# JapaneseLayout_OJP_V0_1_Page_2.net
KiCad netlist of a schematic drawn in Altium Designer
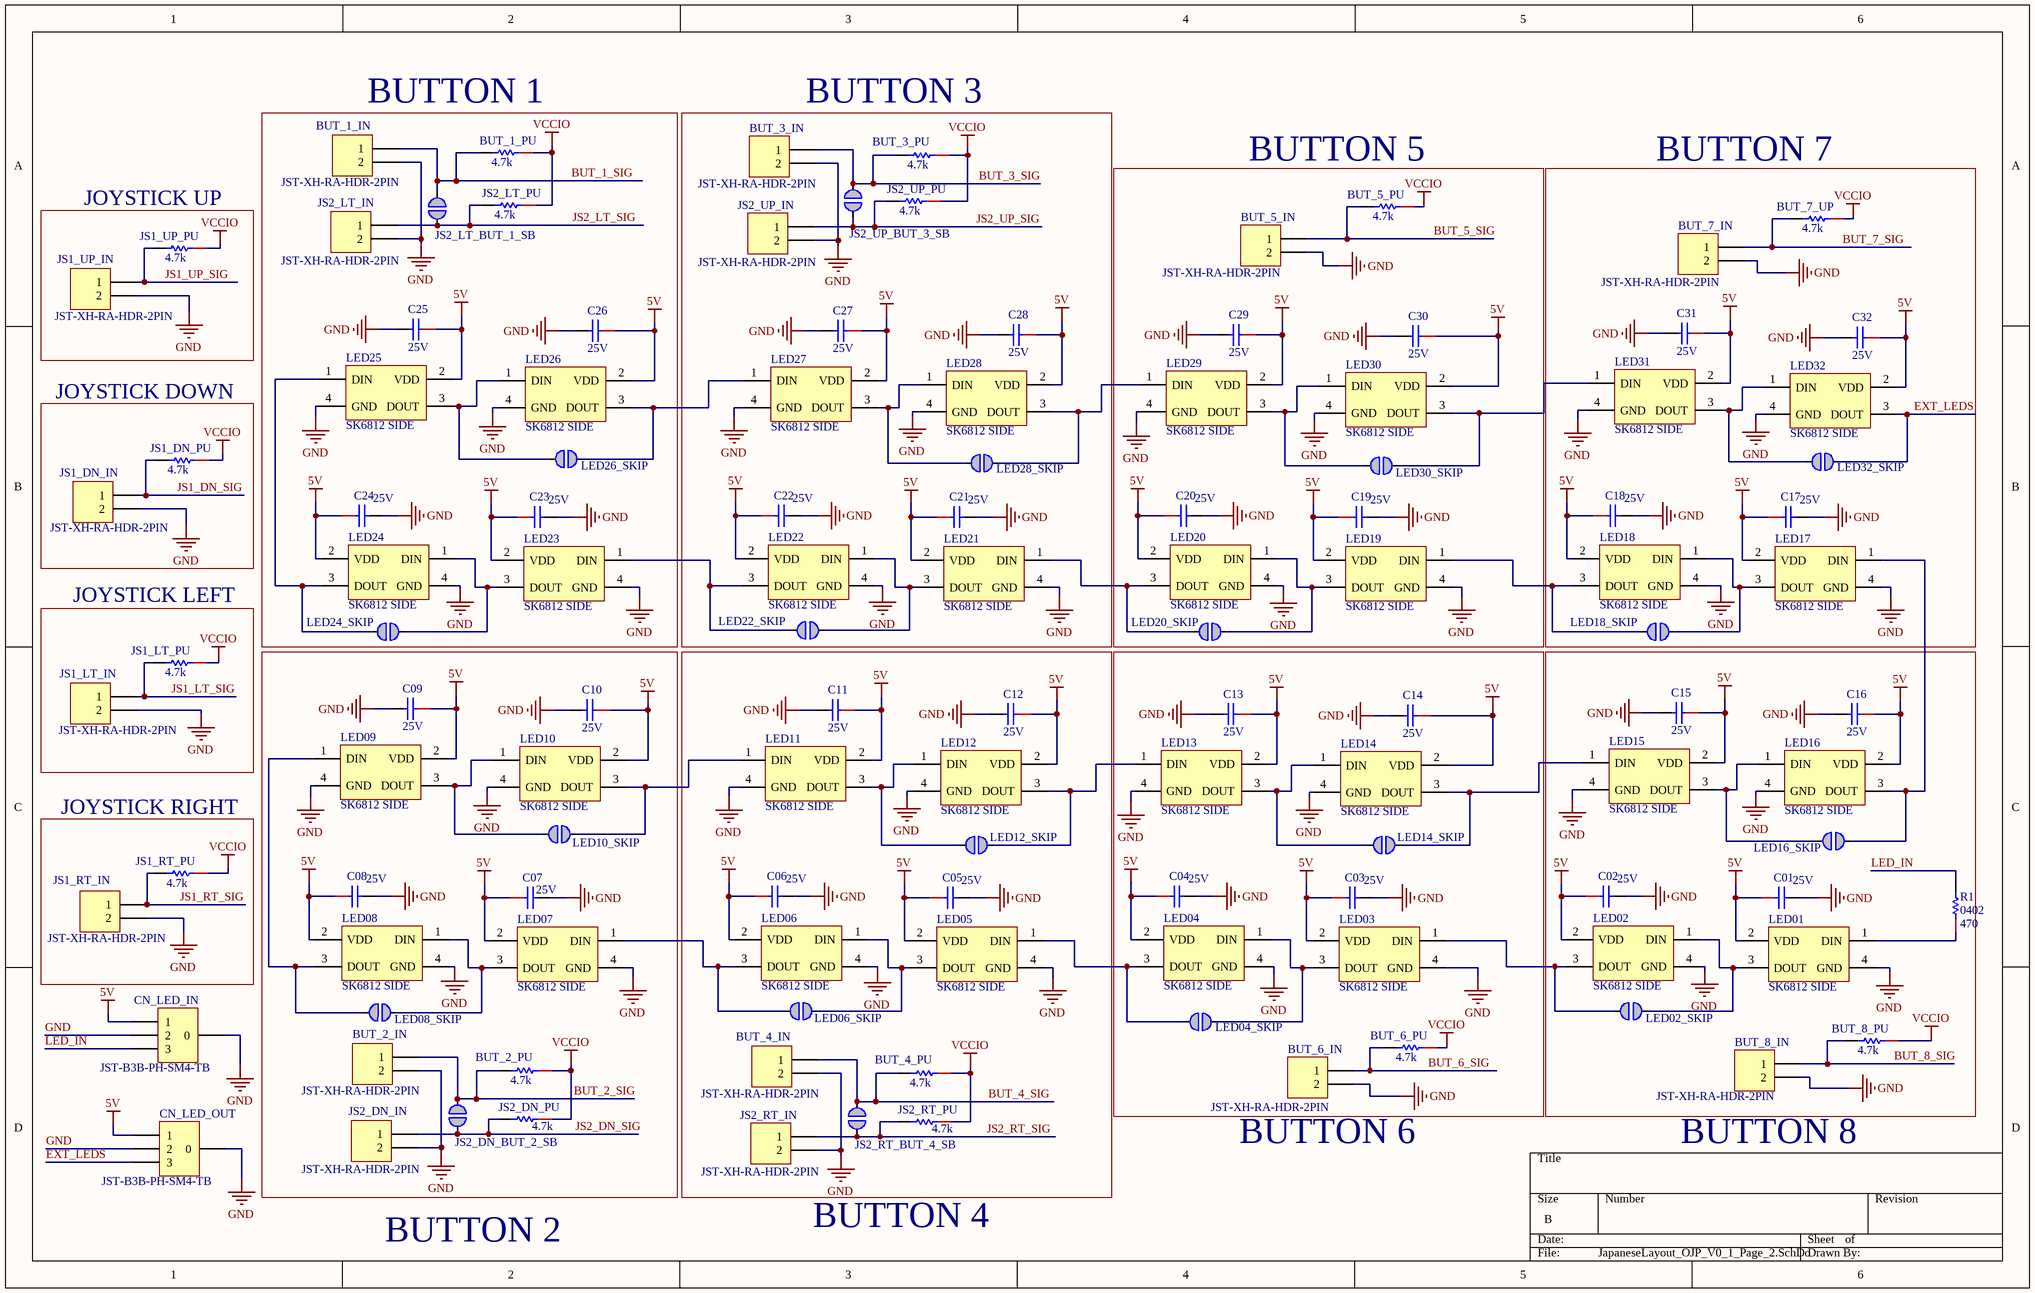
[diagram p0: JapaneseLayout_OJP_V0_1_Page_2.SchDoc]

(export (version "E")
  (design (tool "Eeschema 10.0.6"))
  (components
    (comp (ref "BUT_1_IN")
      (value "JST-XH-RA-HDR-2PIN")
      (footprint "JST-XH-RA-HDR-2PIN")
      (description "2.5 mm JST XH-Style Shrouded Male Connector: 2-Pin, Right Angle; Pololu #2718")
      (libsource (lib "OLogic Nexus Vault") (part "JST-XH-RA-HDR-2PIN"))
    )
    (comp (ref "BUT_1_PU")
      (value "4.7K")
      (footprint "RESC0402(1005)_N")
      (description "RES 4.7K OHM 1% 1/10W 0402")
      (fields
        (field (name "RESISTANCE") "4.7k")
        (field (name "POWER") "100mW")
        (field (name "TOLERANCE") "1%")
      )
      (libsource (lib "OLogic Nexus Vault") (part "=Resistance"))
    )
    (comp (ref "BUT_2_IN")
      (value "JST-XH-RA-HDR-2PIN")
      (footprint "JST-XH-RA-HDR-2PIN")
      (description "2.5 mm JST XH-Style Shrouded Male Connector: 2-Pin, Right Angle; Pololu #2718")
      (libsource (lib "OLogic Nexus Vault") (part "JST-XH-RA-HDR-2PIN"))
    )
    (comp (ref "BUT_2_PU")
      (value "4.7K")
      (footprint "RESC0402(1005)_N")
      (description "RES 4.7K OHM 1% 1/10W 0402")
      (fields
        (field (name "RESISTANCE") "4.7k")
        (field (name "POWER") "100mW")
        (field (name "TOLERANCE") "1%")
      )
      (libsource (lib "OLogic Nexus Vault") (part "=Resistance"))
    )
    (comp (ref "BUT_3_IN")
      (value "JST-XH-RA-HDR-2PIN")
      (footprint "JST-XH-RA-HDR-2PIN")
      (description "2.5 mm JST XH-Style Shrouded Male Connector: 2-Pin, Right Angle; Pololu #2718")
      (libsource (lib "OLogic Nexus Vault") (part "JST-XH-RA-HDR-2PIN"))
    )
    (comp (ref "BUT_3_PU")
      (value "4.7K")
      (footprint "RESC0402(1005)_N")
      (description "RES 4.7K OHM 1% 1/10W 0402")
      (fields
        (field (name "RESISTANCE") "4.7k")
        (field (name "POWER") "100mW")
        (field (name "TOLERANCE") "1%")
      )
      (libsource (lib "OLogic Nexus Vault") (part "=Resistance"))
    )
    (comp (ref "BUT_4_IN")
      (value "JST-XH-RA-HDR-2PIN")
      (footprint "JST-XH-RA-HDR-2PIN")
      (description "2.5 mm JST XH-Style Shrouded Male Connector: 2-Pin, Right Angle; Pololu #2718")
      (libsource (lib "OLogic Nexus Vault") (part "JST-XH-RA-HDR-2PIN"))
    )
    (comp (ref "BUT_4_PU")
      (value "4.7K")
      (footprint "RESC0402(1005)_N")
      (description "RES 4.7K OHM 1% 1/10W 0402")
      (fields
        (field (name "RESISTANCE") "4.7k")
        (field (name "POWER") "100mW")
        (field (name "TOLERANCE") "1%")
      )
      (libsource (lib "OLogic Nexus Vault") (part "=Resistance"))
    )
    (comp (ref "BUT_5_IN")
      (value "JST-XH-RA-HDR-2PIN")
      (footprint "JST-XH-RA-HDR-2PIN")
      (description "2.5 mm JST XH-Style Shrouded Male Connector: 2-Pin, Right Angle; Pololu #2718")
      (libsource (lib "OLogic Nexus Vault") (part "JST-XH-RA-HDR-2PIN"))
    )
    (comp (ref "BUT_5_PU")
      (value "4.7K")
      (footprint "RESC0402(1005)_N")
      (description "RES 4.7K OHM 1% 1/10W 0402")
      (fields
        (field (name "RESISTANCE") "4.7k")
        (field (name "POWER") "100mW")
        (field (name "TOLERANCE") "1%")
      )
      (libsource (lib "OLogic Nexus Vault") (part "=Resistance"))
    )
    (comp (ref "BUT_6_IN")
      (value "JST-XH-RA-HDR-2PIN")
      (footprint "JST-XH-RA-HDR-2PIN")
      (description "2.5 mm JST XH-Style Shrouded Male Connector: 2-Pin, Right Angle; Pololu #2718")
      (libsource (lib "OLogic Nexus Vault") (part "JST-XH-RA-HDR-2PIN"))
    )
    (comp (ref "BUT_6_PU")
      (value "4.7K")
      (footprint "RESC0402(1005)_N")
      (description "RES 4.7K OHM 1% 1/10W 0402")
      (fields
        (field (name "RESISTANCE") "4.7k")
        (field (name "POWER") "100mW")
        (field (name "TOLERANCE") "1%")
      )
      (libsource (lib "OLogic Nexus Vault") (part "=Resistance"))
    )
    (comp (ref "BUT_7_IN")
      (value "JST-XH-RA-HDR-2PIN")
      (footprint "JST-XH-RA-HDR-2PIN")
      (description "2.5 mm JST XH-Style Shrouded Male Connector: 2-Pin, Right Angle; Pololu #2718")
      (libsource (lib "OLogic Nexus Vault") (part "JST-XH-RA-HDR-2PIN"))
    )
    (comp (ref "BUT_7_UP")
      (value "4.7K")
      (footprint "RESC0402(1005)_N")
      (description "RES 4.7K OHM 1% 1/10W 0402")
      (fields
        (field (name "RESISTANCE") "4.7k")
        (field (name "POWER") "100mW")
        (field (name "TOLERANCE") "1%")
      )
      (libsource (lib "OLogic Nexus Vault") (part "=Resistance"))
    )
    (comp (ref "BUT_8_IN")
      (value "JST-XH-RA-HDR-2PIN")
      (footprint "JST-XH-RA-HDR-2PIN")
      (description "2.5 mm JST XH-Style Shrouded Male Connector: 2-Pin, Right Angle; Pololu #2718")
      (libsource (lib "OLogic Nexus Vault") (part "JST-XH-RA-HDR-2PIN"))
    )
    (comp (ref "BUT_8_PU")
      (value "4.7K")
      (footprint "RESC0402(1005)_N")
      (description "RES 4.7K OHM 1% 1/10W 0402")
      (fields
        (field (name "RESISTANCE") "4.7k")
        (field (name "POWER") "100mW")
        (field (name "TOLERANCE") "1%")
      )
      (libsource (lib "OLogic Nexus Vault") (part "=Resistance"))
    )
    (comp (ref "C01")
      (value "CAP CER 0.1UF 25V 10% X5R 0402")
      (footprint "CAPC0402(1005)_N")
      (description "0.1uF 0402 25V")
      (fields
        (field (name "VOLTAGE - RATED") "25V")
        (field (name "MANUFACTURER") "Taiyo Yuden")
        (field (name "MANUFACTURER PART NUMBER") "TMK105BJ104KV-F")
      )
      (libsource (lib "OLogic Nexus Vault") (part "CAP CER 0.1UF 25V 10% X5R 0402"))
    )
    (comp (ref "C02")
      (value "CAP CER 0.1UF 25V 10% X5R 0402")
      (footprint "CAPC0402(1005)_N")
      (description "0.1uF 0402 25V")
      (fields
        (field (name "VOLTAGE - RATED") "25V")
        (field (name "MANUFACTURER") "Taiyo Yuden")
        (field (name "MANUFACTURER PART NUMBER") "TMK105BJ104KV-F")
      )
      (libsource (lib "OLogic Nexus Vault") (part "CAP CER 0.1UF 25V 10% X5R 0402"))
    )
    (comp (ref "C03")
      (value "CAP CER 0.1UF 25V 10% X5R 0402")
      (footprint "CAPC0402(1005)_N")
      (description "0.1uF 0402 25V")
      (fields
        (field (name "VOLTAGE - RATED") "25V")
        (field (name "MANUFACTURER") "Taiyo Yuden")
        (field (name "MANUFACTURER PART NUMBER") "TMK105BJ104KV-F")
      )
      (libsource (lib "OLogic Nexus Vault") (part "CAP CER 0.1UF 25V 10% X5R 0402"))
    )
    (comp (ref "C04")
      (value "CAP CER 0.1UF 25V 10% X5R 0402")
      (footprint "CAPC0402(1005)_N")
      (description "0.1uF 0402 25V")
      (fields
        (field (name "VOLTAGE - RATED") "25V")
        (field (name "MANUFACTURER") "Taiyo Yuden")
        (field (name "MANUFACTURER PART NUMBER") "TMK105BJ104KV-F")
      )
      (libsource (lib "OLogic Nexus Vault") (part "CAP CER 0.1UF 25V 10% X5R 0402"))
    )
    (comp (ref "C05")
      (value "CAP CER 0.1UF 25V 10% X5R 0402")
      (footprint "CAPC0402(1005)_N")
      (description "0.1uF 0402 25V")
      (fields
        (field (name "VOLTAGE - RATED") "25V")
        (field (name "MANUFACTURER") "Taiyo Yuden")
        (field (name "MANUFACTURER PART NUMBER") "TMK105BJ104KV-F")
      )
      (libsource (lib "OLogic Nexus Vault") (part "CAP CER 0.1UF 25V 10% X5R 0402"))
    )
    (comp (ref "C06")
      (value "CAP CER 0.1UF 25V 10% X5R 0402")
      (footprint "CAPC0402(1005)_N")
      (description "0.1uF 0402 25V")
      (fields
        (field (name "VOLTAGE - RATED") "25V")
        (field (name "MANUFACTURER") "Taiyo Yuden")
        (field (name "MANUFACTURER PART NUMBER") "TMK105BJ104KV-F")
      )
      (libsource (lib "OLogic Nexus Vault") (part "CAP CER 0.1UF 25V 10% X5R 0402"))
    )
    (comp (ref "C07")
      (value "CAP CER 0.1UF 25V 10% X5R 0402")
      (footprint "CAPC0402(1005)_N")
      (description "0.1uF 0402 25V")
      (fields
        (field (name "VOLTAGE - RATED") "25V")
        (field (name "MANUFACTURER") "Taiyo Yuden")
        (field (name "MANUFACTURER PART NUMBER") "TMK105BJ104KV-F")
      )
      (libsource (lib "OLogic Nexus Vault") (part "CAP CER 0.1UF 25V 10% X5R 0402"))
    )
    (comp (ref "C08")
      (value "CAP CER 0.1UF 25V 10% X5R 0402")
      (footprint "CAPC0402(1005)_N")
      (description "0.1uF 0402 25V")
      (fields
        (field (name "VOLTAGE - RATED") "25V")
        (field (name "MANUFACTURER") "Taiyo Yuden")
        (field (name "MANUFACTURER PART NUMBER") "TMK105BJ104KV-F")
      )
      (libsource (lib "OLogic Nexus Vault") (part "CAP CER 0.1UF 25V 10% X5R 0402"))
    )
    (comp (ref "C09")
      (value "CAP CER 0.1UF 25V 10% X5R 0402")
      (footprint "CAPC0402(1005)_N")
      (description "0.1uF 0402 25V")
      (fields
        (field (name "VOLTAGE - RATED") "25V")
        (field (name "MANUFACTURER") "Taiyo Yuden")
        (field (name "MANUFACTURER PART NUMBER") "TMK105BJ104KV-F")
      )
      (libsource (lib "OLogic Nexus Vault") (part "CAP CER 0.1UF 25V 10% X5R 0402"))
    )
    (comp (ref "C10")
      (value "CAP CER 0.1UF 25V 10% X5R 0402")
      (footprint "CAPC0402(1005)_N")
      (description "0.1uF 0402 25V")
      (fields
        (field (name "VOLTAGE - RATED") "25V")
        (field (name "MANUFACTURER") "Taiyo Yuden")
        (field (name "MANUFACTURER PART NUMBER") "TMK105BJ104KV-F")
      )
      (libsource (lib "OLogic Nexus Vault") (part "CAP CER 0.1UF 25V 10% X5R 0402"))
    )
    (comp (ref "C11")
      (value "CAP CER 0.1UF 25V 10% X5R 0402")
      (footprint "CAPC0402(1005)_N")
      (description "0.1uF 0402 25V")
      (fields
        (field (name "VOLTAGE - RATED") "25V")
        (field (name "MANUFACTURER") "Taiyo Yuden")
        (field (name "MANUFACTURER PART NUMBER") "TMK105BJ104KV-F")
      )
      (libsource (lib "OLogic Nexus Vault") (part "CAP CER 0.1UF 25V 10% X5R 0402"))
    )
    (comp (ref "C12")
      (value "CAP CER 0.1UF 25V 10% X5R 0402")
      (footprint "CAPC0402(1005)_N")
      (description "0.1uF 0402 25V")
      (fields
        (field (name "VOLTAGE - RATED") "25V")
        (field (name "MANUFACTURER") "Taiyo Yuden")
        (field (name "MANUFACTURER PART NUMBER") "TMK105BJ104KV-F")
      )
      (libsource (lib "OLogic Nexus Vault") (part "CAP CER 0.1UF 25V 10% X5R 0402"))
    )
    (comp (ref "C13")
      (value "CAP CER 0.1UF 25V 10% X5R 0402")
      (footprint "CAPC0402(1005)_N")
      (description "0.1uF 0402 25V")
      (fields
        (field (name "VOLTAGE - RATED") "25V")
        (field (name "MANUFACTURER") "Taiyo Yuden")
        (field (name "MANUFACTURER PART NUMBER") "TMK105BJ104KV-F")
      )
      (libsource (lib "OLogic Nexus Vault") (part "CAP CER 0.1UF 25V 10% X5R 0402"))
    )
    (comp (ref "C14")
      (value "CAP CER 0.1UF 25V 10% X5R 0402")
      (footprint "CAPC0402(1005)_N")
      (description "0.1uF 0402 25V")
      (fields
        (field (name "VOLTAGE - RATED") "25V")
        (field (name "MANUFACTURER") "Taiyo Yuden")
        (field (name "MANUFACTURER PART NUMBER") "TMK105BJ104KV-F")
      )
      (libsource (lib "OLogic Nexus Vault") (part "CAP CER 0.1UF 25V 10% X5R 0402"))
    )
    (comp (ref "C15")
      (value "CAP CER 0.1UF 25V 10% X5R 0402")
      (footprint "CAPC0402(1005)_N")
      (description "0.1uF 0402 25V")
      (fields
        (field (name "VOLTAGE - RATED") "25V")
        (field (name "MANUFACTURER") "Taiyo Yuden")
        (field (name "MANUFACTURER PART NUMBER") "TMK105BJ104KV-F")
      )
      (libsource (lib "OLogic Nexus Vault") (part "CAP CER 0.1UF 25V 10% X5R 0402"))
    )
    (comp (ref "C16")
      (value "CAP CER 0.1UF 25V 10% X5R 0402")
      (footprint "CAPC0402(1005)_N")
      (description "0.1uF 0402 25V")
      (fields
        (field (name "VOLTAGE - RATED") "25V")
        (field (name "MANUFACTURER") "Taiyo Yuden")
        (field (name "MANUFACTURER PART NUMBER") "TMK105BJ104KV-F")
      )
      (libsource (lib "OLogic Nexus Vault") (part "CAP CER 0.1UF 25V 10% X5R 0402"))
    )
    (comp (ref "C17")
      (value "CAP CER 0.1UF 25V 10% X5R 0402")
      (footprint "CAPC0402(1005)_N")
      (description "0.1uF 0402 25V")
      (fields
        (field (name "VOLTAGE - RATED") "25V")
        (field (name "MANUFACTURER") "Taiyo Yuden")
        (field (name "MANUFACTURER PART NUMBER") "TMK105BJ104KV-F")
      )
      (libsource (lib "OLogic Nexus Vault") (part "CAP CER 0.1UF 25V 10% X5R 0402"))
    )
    (comp (ref "C18")
      (value "CAP CER 0.1UF 25V 10% X5R 0402")
      (footprint "CAPC0402(1005)_N")
      (description "0.1uF 0402 25V")
      (fields
        (field (name "VOLTAGE - RATED") "25V")
        (field (name "MANUFACTURER") "Taiyo Yuden")
        (field (name "MANUFACTURER PART NUMBER") "TMK105BJ104KV-F")
      )
      (libsource (lib "OLogic Nexus Vault") (part "CAP CER 0.1UF 25V 10% X5R 0402"))
    )
    (comp (ref "C19")
      (value "CAP CER 0.1UF 25V 10% X5R 0402")
      (footprint "CAPC0402(1005)_N")
      (description "0.1uF 0402 25V")
      (fields
        (field (name "VOLTAGE - RATED") "25V")
        (field (name "MANUFACTURER") "Taiyo Yuden")
        (field (name "MANUFACTURER PART NUMBER") "TMK105BJ104KV-F")
      )
      (libsource (lib "OLogic Nexus Vault") (part "CAP CER 0.1UF 25V 10% X5R 0402"))
    )
    (comp (ref "C20")
      (value "CAP CER 0.1UF 25V 10% X5R 0402")
      (footprint "CAPC0402(1005)_N")
      (description "0.1uF 0402 25V")
      (fields
        (field (name "VOLTAGE - RATED") "25V")
        (field (name "MANUFACTURER") "Taiyo Yuden")
        (field (name "MANUFACTURER PART NUMBER") "TMK105BJ104KV-F")
      )
      (libsource (lib "OLogic Nexus Vault") (part "CAP CER 0.1UF 25V 10% X5R 0402"))
    )
    (comp (ref "C21")
      (value "CAP CER 0.1UF 25V 10% X5R 0402")
      (footprint "CAPC0402(1005)_N")
      (description "0.1uF 0402 25V")
      (fields
        (field (name "VOLTAGE - RATED") "25V")
        (field (name "MANUFACTURER") "Taiyo Yuden")
        (field (name "MANUFACTURER PART NUMBER") "TMK105BJ104KV-F")
      )
      (libsource (lib "OLogic Nexus Vault") (part "CAP CER 0.1UF 25V 10% X5R 0402"))
    )
    (comp (ref "C22")
      (value "CAP CER 0.1UF 25V 10% X5R 0402")
      (footprint "CAPC0402(1005)_N")
      (description "0.1uF 0402 25V")
      (fields
        (field (name "VOLTAGE - RATED") "25V")
        (field (name "MANUFACTURER") "Taiyo Yuden")
        (field (name "MANUFACTURER PART NUMBER") "TMK105BJ104KV-F")
      )
      (libsource (lib "OLogic Nexus Vault") (part "CAP CER 0.1UF 25V 10% X5R 0402"))
    )
    (comp (ref "C23")
      (value "CAP CER 0.1UF 25V 10% X5R 0402")
      (footprint "CAPC0402(1005)_N")
      (description "0.1uF 0402 25V")
      (fields
        (field (name "VOLTAGE - RATED") "25V")
        (field (name "MANUFACTURER") "Taiyo Yuden")
        (field (name "MANUFACTURER PART NUMBER") "TMK105BJ104KV-F")
      )
      (libsource (lib "OLogic Nexus Vault") (part "CAP CER 0.1UF 25V 10% X5R 0402"))
    )
    (comp (ref "C24")
      (value "CAP CER 0.1UF 25V 10% X5R 0402")
      (footprint "CAPC0402(1005)_N")
      (description "0.1uF 0402 25V")
      (fields
        (field (name "VOLTAGE - RATED") "25V")
        (field (name "MANUFACTURER") "Taiyo Yuden")
        (field (name "MANUFACTURER PART NUMBER") "TMK105BJ104KV-F")
      )
      (libsource (lib "OLogic Nexus Vault") (part "CAP CER 0.1UF 25V 10% X5R 0402"))
    )
    (comp (ref "C25")
      (value "CAP CER 0.1UF 25V 10% X5R 0402")
      (footprint "CAPC0402(1005)_N")
      (description "0.1uF 0402 25V")
      (fields
        (field (name "VOLTAGE - RATED") "25V")
        (field (name "MANUFACTURER") "Taiyo Yuden")
        (field (name "MANUFACTURER PART NUMBER") "TMK105BJ104KV-F")
      )
      (libsource (lib "OLogic Nexus Vault") (part "CAP CER 0.1UF 25V 10% X5R 0402"))
    )
    (comp (ref "C26")
      (value "CAP CER 0.1UF 25V 10% X5R 0402")
      (footprint "CAPC0402(1005)_N")
      (description "0.1uF 0402 25V")
      (fields
        (field (name "VOLTAGE - RATED") "25V")
        (field (name "MANUFACTURER") "Taiyo Yuden")
        (field (name "MANUFACTURER PART NUMBER") "TMK105BJ104KV-F")
      )
      (libsource (lib "OLogic Nexus Vault") (part "CAP CER 0.1UF 25V 10% X5R 0402"))
    )
    (comp (ref "C27")
      (value "CAP CER 0.1UF 25V 10% X5R 0402")
      (footprint "CAPC0402(1005)_N")
      (description "0.1uF 0402 25V")
      (fields
        (field (name "VOLTAGE - RATED") "25V")
        (field (name "MANUFACTURER") "Taiyo Yuden")
        (field (name "MANUFACTURER PART NUMBER") "TMK105BJ104KV-F")
      )
      (libsource (lib "OLogic Nexus Vault") (part "CAP CER 0.1UF 25V 10% X5R 0402"))
    )
    (comp (ref "C28")
      (value "CAP CER 0.1UF 25V 10% X5R 0402")
      (footprint "CAPC0402(1005)_N")
      (description "0.1uF 0402 25V")
      (fields
        (field (name "VOLTAGE - RATED") "25V")
        (field (name "MANUFACTURER") "Taiyo Yuden")
        (field (name "MANUFACTURER PART NUMBER") "TMK105BJ104KV-F")
      )
      (libsource (lib "OLogic Nexus Vault") (part "CAP CER 0.1UF 25V 10% X5R 0402"))
    )
    (comp (ref "C29")
      (value "CAP CER 0.1UF 25V 10% X5R 0402")
      (footprint "CAPC0402(1005)_N")
      (description "0.1uF 0402 25V")
      (fields
        (field (name "VOLTAGE - RATED") "25V")
        (field (name "MANUFACTURER") "Taiyo Yuden")
        (field (name "MANUFACTURER PART NUMBER") "TMK105BJ104KV-F")
      )
      (libsource (lib "OLogic Nexus Vault") (part "CAP CER 0.1UF 25V 10% X5R 0402"))
    )
    (comp (ref "C30")
      (value "CAP CER 0.1UF 25V 10% X5R 0402")
      (footprint "CAPC0402(1005)_N")
      (description "0.1uF 0402 25V")
      (fields
        (field (name "VOLTAGE - RATED") "25V")
        (field (name "MANUFACTURER") "Taiyo Yuden")
        (field (name "MANUFACTURER PART NUMBER") "TMK105BJ104KV-F")
      )
      (libsource (lib "OLogic Nexus Vault") (part "CAP CER 0.1UF 25V 10% X5R 0402"))
    )
    (comp (ref "C31")
      (value "CAP CER 0.1UF 25V 10% X5R 0402")
      (footprint "CAPC0402(1005)_N")
      (description "0.1uF 0402 25V")
      (fields
        (field (name "VOLTAGE - RATED") "25V")
        (field (name "MANUFACTURER") "Taiyo Yuden")
        (field (name "MANUFACTURER PART NUMBER") "TMK105BJ104KV-F")
      )
      (libsource (lib "OLogic Nexus Vault") (part "CAP CER 0.1UF 25V 10% X5R 0402"))
    )
    (comp (ref "C32")
      (value "CAP CER 0.1UF 25V 10% X5R 0402")
      (footprint "CAPC0402(1005)_N")
      (description "0.1uF 0402 25V")
      (fields
        (field (name "VOLTAGE - RATED") "25V")
        (field (name "MANUFACTURER") "Taiyo Yuden")
        (field (name "MANUFACTURER PART NUMBER") "TMK105BJ104KV-F")
      )
      (libsource (lib "OLogic Nexus Vault") (part "CAP CER 0.1UF 25V 10% X5R 0402"))
    )
    (comp (ref "CN_LED_IN")
      (value "JST-B3B-PH-SM4-TB")
      (footprint "JST-B3B-PH-SM4-TB")
      (description "2mm Locking Header, 3-Pin")
      (fields
        (field (name "MANUFACTURER PART NUMBER") "B3B-PH-SM4-TB(LF)(SN)(P)")
        (field (name "MANUFACTURER") "JST Sales America Inc")
      )
      (libsource (lib "OLogic Nexus Vault") (part "JST-B3B-PH-SM4-TB"))
    )
    (comp (ref "CN_LED_OUT")
      (value "JST-B3B-PH-SM4-TB")
      (footprint "JST-B3B-PH-SM4-TB")
      (description "2mm Locking Header, 3-Pin")
      (fields
        (field (name "MANUFACTURER PART NUMBER") "B3B-PH-SM4-TB(LF)(SN)(P)")
        (field (name "MANUFACTURER") "JST Sales America Inc")
      )
      (libsource (lib "OLogic Nexus Vault") (part "JST-B3B-PH-SM4-TB"))
    )
    (comp (ref "JS1_DN_IN")
      (value "JST-XH-RA-HDR-2PIN")
      (footprint "JST-XH-RA-HDR-2PIN")
      (description "2.5 mm JST XH-Style Shrouded Male Connector: 2-Pin, Right Angle; Pololu #2718")
      (libsource (lib "OLogic Nexus Vault") (part "JST-XH-RA-HDR-2PIN"))
    )
    (comp (ref "JS1_DN_PU")
      (value "4.7K")
      (footprint "RESC0402(1005)_N")
      (description "RES 4.7K OHM 1% 1/10W 0402")
      (fields
        (field (name "RESISTANCE") "4.7k")
        (field (name "POWER") "100mW")
        (field (name "TOLERANCE") "1%")
      )
      (libsource (lib "OLogic Nexus Vault") (part "=Resistance"))
    )
    (comp (ref "JS1_LT_IN")
      (value "JST-XH-RA-HDR-2PIN")
      (footprint "JST-XH-RA-HDR-2PIN")
      (description "2.5 mm JST XH-Style Shrouded Male Connector: 2-Pin, Right Angle; Pololu #2718")
      (libsource (lib "OLogic Nexus Vault") (part "JST-XH-RA-HDR-2PIN"))
    )
    (comp (ref "JS1_LT_PU")
      (value "4.7K")
      (footprint "RESC0402(1005)_N")
      (description "RES 4.7K OHM 1% 1/10W 0402")
      (fields
        (field (name "RESISTANCE") "4.7k")
        (field (name "POWER") "100mW")
        (field (name "TOLERANCE") "1%")
      )
      (libsource (lib "OLogic Nexus Vault") (part "=Resistance"))
    )
    (comp (ref "JS1_RT_IN")
      (value "JST-XH-RA-HDR-2PIN")
      (footprint "JST-XH-RA-HDR-2PIN")
      (description "2.5 mm JST XH-Style Shrouded Male Connector: 2-Pin, Right Angle; Pololu #2718")
      (libsource (lib "OLogic Nexus Vault") (part "JST-XH-RA-HDR-2PIN"))
    )
    (comp (ref "JS1_RT_PU")
      (value "4.7K")
      (footprint "RESC0402(1005)_N")
      (description "RES 4.7K OHM 1% 1/10W 0402")
      (fields
        (field (name "RESISTANCE") "4.7k")
        (field (name "POWER") "100mW")
        (field (name "TOLERANCE") "1%")
      )
      (libsource (lib "OLogic Nexus Vault") (part "=Resistance"))
    )
    (comp (ref "JS1_UP_IN")
      (value "JST-XH-RA-HDR-2PIN")
      (footprint "JST-XH-RA-HDR-2PIN")
      (description "2.5 mm JST XH-Style Shrouded Male Connector: 2-Pin, Right Angle; Pololu #2718")
      (libsource (lib "OLogic Nexus Vault") (part "JST-XH-RA-HDR-2PIN"))
    )
    (comp (ref "JS1_UP_PU")
      (value "4.7K")
      (footprint "RESC0402(1005)_N")
      (description "RES 4.7K OHM 1% 1/10W 0402")
      (fields
        (field (name "RESISTANCE") "4.7k")
        (field (name "POWER") "100mW")
        (field (name "TOLERANCE") "1%")
      )
      (libsource (lib "OLogic Nexus Vault") (part "=Resistance"))
    )
    (comp (ref "JS2_DN_BUT_2_SB")
      (value "SOLDERBRIDGE")
      (footprint "Solderbridge")
      (description "Solderbridge")
      (fields (field (name "PUBLISHER") "Nordic Semiconductor"))
      (libsource (lib "OLogic Nexus Vault") (part "SOLDERBRIDGE"))
    )
    (comp (ref "JS2_DN_IN")
      (value "JST-XH-RA-HDR-2PIN")
      (footprint "JST-XH-RA-HDR-2PIN")
      (description "2.5 mm JST XH-Style Shrouded Male Connector: 2-Pin, Right Angle; Pololu #2718")
      (libsource (lib "OLogic Nexus Vault") (part "JST-XH-RA-HDR-2PIN"))
    )
    (comp (ref "JS2_DN_PU")
      (value "4.7K")
      (footprint "RESC0402(1005)_N")
      (description "RES 4.7K OHM 1% 1/10W 0402")
      (fields
        (field (name "RESISTANCE") "4.7k")
        (field (name "POWER") "100mW")
        (field (name "TOLERANCE") "1%")
      )
      (libsource (lib "OLogic Nexus Vault") (part "=Resistance"))
    )
    (comp (ref "JS2_LT_BUT_1_SB")
      (value "SOLDERBRIDGE")
      (footprint "Solderbridge")
      (description "Solderbridge")
      (fields (field (name "PUBLISHER") "Nordic Semiconductor"))
      (libsource (lib "OLogic Nexus Vault") (part "SOLDERBRIDGE"))
    )
    (comp (ref "JS2_LT_IN")
      (value "JST-XH-RA-HDR-2PIN")
      (footprint "JST-XH-RA-HDR-2PIN")
      (description "2.5 mm JST XH-Style Shrouded Male Connector: 2-Pin, Right Angle; Pololu #2718")
      (libsource (lib "OLogic Nexus Vault") (part "JST-XH-RA-HDR-2PIN"))
    )
    (comp (ref "JS2_LT_PU")
      (value "4.7K")
      (footprint "RESC0402(1005)_N")
      (description "RES 4.7K OHM 1% 1/10W 0402")
      (fields
        (field (name "RESISTANCE") "4.7k")
        (field (name "POWER") "100mW")
        (field (name "TOLERANCE") "1%")
      )
      (libsource (lib "OLogic Nexus Vault") (part "=Resistance"))
    )
    (comp (ref "JS2_RT_BUT_4_SB")
      (value "SOLDERBRIDGE")
      (footprint "Solderbridge")
      (description "Solderbridge")
      (fields (field (name "PUBLISHER") "Nordic Semiconductor"))
      (libsource (lib "OLogic Nexus Vault") (part "SOLDERBRIDGE"))
    )
    (comp (ref "JS2_RT_IN")
      (value "JST-XH-RA-HDR-2PIN")
      (footprint "JST-XH-RA-HDR-2PIN")
      (description "2.5 mm JST XH-Style Shrouded Male Connector: 2-Pin, Right Angle; Pololu #2718")
      (libsource (lib "OLogic Nexus Vault") (part "JST-XH-RA-HDR-2PIN"))
    )
    (comp (ref "JS2_RT_PU")
      (value "4.7K")
      (footprint "RESC0402(1005)_N")
      (description "RES 4.7K OHM 1% 1/10W 0402")
      (fields
        (field (name "RESISTANCE") "4.7k")
        (field (name "POWER") "100mW")
        (field (name "TOLERANCE") "1%")
      )
      (libsource (lib "OLogic Nexus Vault") (part "=Resistance"))
    )
    (comp (ref "JS2_UP_BUT_3_SB")
      (value "SOLDERBRIDGE")
      (footprint "Solderbridge")
      (description "Solderbridge")
      (fields (field (name "PUBLISHER") "Nordic Semiconductor"))
      (libsource (lib "OLogic Nexus Vault") (part "SOLDERBRIDGE"))
    )
    (comp (ref "JS2_UP_IN")
      (value "JST-XH-RA-HDR-2PIN")
      (footprint "JST-XH-RA-HDR-2PIN")
      (description "2.5 mm JST XH-Style Shrouded Male Connector: 2-Pin, Right Angle; Pololu #2718")
      (libsource (lib "OLogic Nexus Vault") (part "JST-XH-RA-HDR-2PIN"))
    )
    (comp (ref "JS2_UP_PU")
      (value "4.7K")
      (footprint "RESC0402(1005)_N")
      (description "RES 4.7K OHM 1% 1/10W 0402")
      (fields
        (field (name "RESISTANCE") "4.7k")
        (field (name "POWER") "100mW")
        (field (name "TOLERANCE") "1%")
      )
      (libsource (lib "OLogic Nexus Vault") (part "=Resistance"))
    )
    (comp (ref "LED01")
      (value "SK6812 SIDE")
      (footprint "SOT-553")
      (description "SK6812 SIDE 4020 RGB LED")
      (libsource (lib "OLogic Nexus Vault") (part "SK6812"))
    )
    (comp (ref "LED02")
      (value "SK6812 SIDE")
      (footprint "SOT-553")
      (description "SK6812 SIDE 4020 RGB LED")
      (libsource (lib "OLogic Nexus Vault") (part "SK6812"))
    )
    (comp (ref "LED02_SKIP")
      (value "SOLDERBRIDGE")
      (footprint "Solderbridge")
      (description "Solderbridge")
      (fields (field (name "PUBLISHER") "Nordic Semiconductor"))
      (libsource (lib "OLogic Nexus Vault") (part "SOLDERBRIDGE"))
    )
    (comp (ref "LED03")
      (value "SK6812 SIDE")
      (footprint "SOT-553")
      (description "SK6812 SIDE 4020 RGB LED")
      (libsource (lib "OLogic Nexus Vault") (part "SK6812"))
    )
    (comp (ref "LED04")
      (value "SK6812 SIDE")
      (footprint "SOT-553")
      (description "SK6812 SIDE 4020 RGB LED")
      (libsource (lib "OLogic Nexus Vault") (part "SK6812"))
    )
    (comp (ref "LED04_SKIP")
      (value "SOLDERBRIDGE")
      (footprint "Solderbridge")
      (description "Solderbridge")
      (fields (field (name "PUBLISHER") "Nordic Semiconductor"))
      (libsource (lib "OLogic Nexus Vault") (part "SOLDERBRIDGE"))
    )
    (comp (ref "LED05")
      (value "SK6812 SIDE")
      (footprint "SOT-553")
      (description "SK6812 SIDE 4020 RGB LED")
      (libsource (lib "OLogic Nexus Vault") (part "SK6812"))
    )
    (comp (ref "LED06")
      (value "SK6812 SIDE")
      (footprint "SOT-553")
      (description "SK6812 SIDE 4020 RGB LED")
      (libsource (lib "OLogic Nexus Vault") (part "SK6812"))
    )
    (comp (ref "LED06_SKIP")
      (value "SOLDERBRIDGE")
      (footprint "Solderbridge")
      (description "Solderbridge")
      (fields (field (name "PUBLISHER") "Nordic Semiconductor"))
      (libsource (lib "OLogic Nexus Vault") (part "SOLDERBRIDGE"))
    )
    (comp (ref "LED07")
      (value "SK6812 SIDE")
      (footprint "SOT-553")
      (description "SK6812 SIDE 4020 RGB LED")
      (libsource (lib "OLogic Nexus Vault") (part "SK6812"))
    )
    (comp (ref "LED08")
      (value "SK6812 SIDE")
      (footprint "SOT-553")
      (description "SK6812 SIDE 4020 RGB LED")
      (libsource (lib "OLogic Nexus Vault") (part "SK6812"))
    )
    (comp (ref "LED08_SKIP")
      (value "SOLDERBRIDGE")
      (footprint "Solderbridge")
      (description "Solderbridge")
      (fields (field (name "PUBLISHER") "Nordic Semiconductor"))
      (libsource (lib "OLogic Nexus Vault") (part "SOLDERBRIDGE"))
    )
    (comp (ref "LED09")
      (value "SK6812 SIDE")
      (footprint "SOT-553")
      (description "SK6812 SIDE 4020 RGB LED")
      (libsource (lib "") (part "SK6812_1"))
    )
    (comp (ref "LED10")
      (value "SK6812 SIDE")
      (footprint "SOT-553")
      (description "SK6812 SIDE 4020 RGB LED")
      (libsource (lib "") (part "SK6812_1"))
    )
    (comp (ref "LED10_SKIP")
      (value "SOLDERBRIDGE")
      (footprint "Solderbridge")
      (description "Solderbridge")
      (fields (field (name "PUBLISHER") "Nordic Semiconductor"))
      (libsource (lib "OLogic Nexus Vault") (part "SOLDERBRIDGE"))
    )
    (comp (ref "LED11")
      (value "SK6812 SIDE")
      (footprint "SOT-553")
      (description "SK6812 SIDE 4020 RGB LED")
      (libsource (lib "") (part "SK6812_1"))
    )
    (comp (ref "LED12")
      (value "SK6812 SIDE")
      (footprint "SOT-553")
      (description "SK6812 SIDE 4020 RGB LED")
      (libsource (lib "") (part "SK6812_1"))
    )
    (comp (ref "LED12_SKIP")
      (value "SOLDERBRIDGE")
      (footprint "Solderbridge")
      (description "Solderbridge")
      (fields (field (name "PUBLISHER") "Nordic Semiconductor"))
      (libsource (lib "OLogic Nexus Vault") (part "SOLDERBRIDGE"))
    )
    (comp (ref "LED13")
      (value "SK6812 SIDE")
      (footprint "SOT-553")
      (description "SK6812 SIDE 4020 RGB LED")
      (libsource (lib "") (part "SK6812_1"))
    )
    (comp (ref "LED14")
      (value "SK6812 SIDE")
      (footprint "SOT-553")
      (description "SK6812 SIDE 4020 RGB LED")
      (libsource (lib "") (part "SK6812_1"))
    )
    (comp (ref "LED14_SKIP")
      (value "SOLDERBRIDGE")
      (footprint "Solderbridge")
      (description "Solderbridge")
      (fields (field (name "PUBLISHER") "Nordic Semiconductor"))
      (libsource (lib "OLogic Nexus Vault") (part "SOLDERBRIDGE"))
    )
    (comp (ref "LED15")
      (value "SK6812 SIDE")
      (footprint "SOT-553")
      (description "SK6812 SIDE 4020 RGB LED")
      (libsource (lib "") (part "SK6812_1"))
    )
    (comp (ref "LED16")
      (value "SK6812 SIDE")
      (footprint "SOT-553")
      (description "SK6812 SIDE 4020 RGB LED")
      (libsource (lib "") (part "SK6812_1"))
    )
    (comp (ref "LED16_SKIP")
      (value "SOLDERBRIDGE")
      (footprint "Solderbridge")
      (description "Solderbridge")
      (fields (field (name "PUBLISHER") "Nordic Semiconductor"))
      (libsource (lib "OLogic Nexus Vault") (part "SOLDERBRIDGE"))
    )
    (comp (ref "LED17")
      (value "SK6812 SIDE")
      (footprint "SOT-553")
      (description "SK6812 SIDE 4020 RGB LED")
      (libsource (lib "OLogic Nexus Vault") (part "SK6812"))
    )
    (comp (ref "LED18")
      (value "SK6812 SIDE")
      (footprint "SOT-553")
      (description "SK6812 SIDE 4020 RGB LED")
      (libsource (lib "OLogic Nexus Vault") (part "SK6812"))
    )
    (comp (ref "LED18_SKIP")
      (value "SOLDERBRIDGE")
      (footprint "Solderbridge")
      (description "Solderbridge")
      (fields (field (name "PUBLISHER") "Nordic Semiconductor"))
      (libsource (lib "OLogic Nexus Vault") (part "SOLDERBRIDGE"))
    )
    (comp (ref "LED19")
      (value "SK6812 SIDE")
      (footprint "SOT-553")
      (description "SK6812 SIDE 4020 RGB LED")
      (libsource (lib "OLogic Nexus Vault") (part "SK6812"))
    )
    (comp (ref "LED20")
      (value "SK6812 SIDE")
      (footprint "SOT-553")
      (description "SK6812 SIDE 4020 RGB LED")
      (libsource (lib "OLogic Nexus Vault") (part "SK6812"))
    )
    (comp (ref "LED20_SKIP")
      (value "SOLDERBRIDGE")
      (footprint "Solderbridge")
      (description "Solderbridge")
      (fields (field (name "PUBLISHER") "Nordic Semiconductor"))
      (libsource (lib "OLogic Nexus Vault") (part "SOLDERBRIDGE"))
    )
    (comp (ref "LED21")
      (value "SK6812 SIDE")
      (footprint "SOT-553")
      (description "SK6812 SIDE 4020 RGB LED")
      (libsource (lib "OLogic Nexus Vault") (part "SK6812"))
    )
    (comp (ref "LED22")
      (value "SK6812 SIDE")
      (footprint "SOT-553")
      (description "SK6812 SIDE 4020 RGB LED")
      (libsource (lib "OLogic Nexus Vault") (part "SK6812"))
    )
    (comp (ref "LED22_SKIP")
      (value "SOLDERBRIDGE")
      (footprint "Solderbridge")
      (description "Solderbridge")
      (fields (field (name "PUBLISHER") "Nordic Semiconductor"))
      (libsource (lib "OLogic Nexus Vault") (part "SOLDERBRIDGE"))
    )
    (comp (ref "LED23")
      (value "SK6812 SIDE")
      (footprint "SOT-553")
      (description "SK6812 SIDE 4020 RGB LED")
      (libsource (lib "OLogic Nexus Vault") (part "SK6812"))
    )
    (comp (ref "LED24")
      (value "SK6812 SIDE")
      (footprint "SOT-553")
      (description "SK6812 SIDE 4020 RGB LED")
      (libsource (lib "OLogic Nexus Vault") (part "SK6812"))
    )
    (comp (ref "LED24_SKIP")
      (value "SOLDERBRIDGE")
      (footprint "Solderbridge")
      (description "Solderbridge")
      (fields (field (name "PUBLISHER") "Nordic Semiconductor"))
      (libsource (lib "OLogic Nexus Vault") (part "SOLDERBRIDGE"))
    )
    (comp (ref "LED25")
      (value "SK6812 SIDE")
      (footprint "SOT-553")
      (description "SK6812 SIDE 4020 RGB LED")
      (libsource (lib "") (part "SK6812_1"))
    )
    (comp (ref "LED26")
      (value "SK6812 SIDE")
      (footprint "SOT-553")
      (description "SK6812 SIDE 4020 RGB LED")
      (libsource (lib "") (part "SK6812_1"))
    )
    (comp (ref "LED26_SKIP")
      (value "SOLDERBRIDGE")
      (footprint "Solderbridge")
      (description "Solderbridge")
      (fields (field (name "PUBLISHER") "Nordic Semiconductor"))
      (libsource (lib "OLogic Nexus Vault") (part "SOLDERBRIDGE"))
    )
    (comp (ref "LED27")
      (value "SK6812 SIDE")
      (footprint "SOT-553")
      (description "SK6812 SIDE 4020 RGB LED")
      (libsource (lib "") (part "SK6812_1"))
    )
    (comp (ref "LED28")
      (value "SK6812 SIDE")
      (footprint "SOT-553")
      (description "SK6812 SIDE 4020 RGB LED")
      (libsource (lib "") (part "SK6812_1"))
    )
    (comp (ref "LED28_SKIP")
      (value "SOLDERBRIDGE")
      (footprint "Solderbridge")
      (description "Solderbridge")
      (fields (field (name "PUBLISHER") "Nordic Semiconductor"))
      (libsource (lib "OLogic Nexus Vault") (part "SOLDERBRIDGE"))
    )
    (comp (ref "LED29")
      (value "SK6812 SIDE")
      (footprint "SOT-553")
      (description "SK6812 SIDE 4020 RGB LED")
      (libsource (lib "") (part "SK6812_1"))
    )
    (comp (ref "LED30")
      (value "SK6812 SIDE")
      (footprint "SOT-553")
      (description "SK6812 SIDE 4020 RGB LED")
      (libsource (lib "") (part "SK6812_1"))
    )
    (comp (ref "LED30_SKIP")
      (value "SOLDERBRIDGE")
      (footprint "Solderbridge")
      (description "Solderbridge")
      (fields (field (name "PUBLISHER") "Nordic Semiconductor"))
      (libsource (lib "OLogic Nexus Vault") (part "SOLDERBRIDGE"))
    )
    (comp (ref "LED31")
      (value "SK6812 SIDE")
      (footprint "SOT-553")
      (description "SK6812 SIDE 4020 RGB LED")
      (libsource (lib "") (part "SK6812_1"))
    )
    (comp (ref "LED32")
      (value "SK6812 SIDE")
      (footprint "SOT-553")
      (description "SK6812 SIDE 4020 RGB LED")
      (libsource (lib "") (part "SK6812_1"))
    )
    (comp (ref "LED32_SKIP")
      (value "SOLDERBRIDGE")
      (footprint "Solderbridge")
      (description "Solderbridge")
      (fields (field (name "PUBLISHER") "Nordic Semiconductor"))
      (libsource (lib "OLogic Nexus Vault") (part "SOLDERBRIDGE"))
    )
    (comp (ref "R1")
      (value "470")
      (footprint "RESC0402(1005)_M")
      (description "RES 470 OHM 1% 1/10W 0402")
      (fields
        (field (name "PACKAGE (IMPERIAL)") "0402")
        (field (name "POWER") "63mW")
        (field (name "TOLERANCE") "1%")
        (field (name "RESISTANCE") "470")
      )
      (libsource (lib "OLogic Nexus Vault") (part "=Resistance"))
    )
  )
  (nets
    (net (code "1") (name "/BUT_1_SIG") (class "Default")
      (node (ref "BUT_1_IN") (pin "1") (pinfunction "1_1") (pintype "passive"))
      (node (ref "BUT_1_PU") (pin "2") (pinfunction "2_2") (pintype "passive"))
      (node (ref "JS2_LT_BUT_1_SB") (pin "1") (pinfunction "0_1") (pintype "passive"))
    )
    (net (code "2") (name "/BUT_2_SIG") (class "Default")
      (node (ref "BUT_2_IN") (pin "1") (pinfunction "1_1") (pintype "passive"))
      (node (ref "BUT_2_PU") (pin "2") (pinfunction "2_2") (pintype "passive"))
      (node (ref "JS2_DN_BUT_2_SB") (pin "1") (pinfunction "0_1") (pintype "passive"))
    )
    (net (code "3") (name "/BUT_3_SIG") (class "Default")
      (node (ref "BUT_3_IN") (pin "1") (pinfunction "1_1") (pintype "passive"))
      (node (ref "BUT_3_PU") (pin "2") (pinfunction "2_2") (pintype "passive"))
      (node (ref "JS2_UP_BUT_3_SB") (pin "1") (pinfunction "0_1") (pintype "passive"))
    )
    (net (code "4") (name "/BUT_4_SIG") (class "Default")
      (node (ref "BUT_4_IN") (pin "1") (pinfunction "1_1") (pintype "passive"))
      (node (ref "BUT_4_PU") (pin "2") (pinfunction "2_2") (pintype "passive"))
      (node (ref "JS2_RT_BUT_4_SB") (pin "1") (pinfunction "0_1") (pintype "passive"))
    )
    (net (code "5") (name "/BUT_5_SIG") (class "Default")
      (node (ref "BUT_5_IN") (pin "1") (pinfunction "1_1") (pintype "passive"))
      (node (ref "BUT_5_PU") (pin "2") (pinfunction "2_2") (pintype "passive"))
    )
    (net (code "6") (name "/BUT_6_SIG") (class "Default")
      (node (ref "BUT_6_IN") (pin "1") (pinfunction "1_1") (pintype "passive"))
      (node (ref "BUT_6_PU") (pin "2") (pinfunction "2_2") (pintype "passive"))
    )
    (net (code "7") (name "/BUT_7_SIG") (class "Default")
      (node (ref "BUT_7_IN") (pin "1") (pinfunction "1_1") (pintype "passive"))
      (node (ref "BUT_7_UP") (pin "2") (pinfunction "2_2") (pintype "passive"))
    )
    (net (code "8") (name "/BUT_8_SIG") (class "Default")
      (node (ref "BUT_8_IN") (pin "1") (pinfunction "1_1") (pintype "passive"))
      (node (ref "BUT_8_PU") (pin "2") (pinfunction "2_2") (pintype "passive"))
    )
    (net (code "9") (name "/EXT_LEDS") (class "Default")
      (node (ref "CN_LED_OUT") (pin "3") (pinfunction "3_3") (pintype "passive"))
      (node (ref "LED32") (pin "3") (pinfunction "DOUT_3") (pintype "power_in"))
      (node (ref "LED32_SKIP") (pin "1") (pinfunction "0_1") (pintype "passive"))
    )
    (net (code "10") (name "/JS1_DN_SIG") (class "Default")
      (node (ref "JS1_DN_IN") (pin "1") (pinfunction "1_1") (pintype "passive"))
      (node (ref "JS1_DN_PU") (pin "2") (pinfunction "2_2") (pintype "passive"))
    )
    (net (code "11") (name "/JS1_LT_SIG") (class "Default")
      (node (ref "JS1_LT_IN") (pin "1") (pinfunction "1_1") (pintype "passive"))
      (node (ref "JS1_LT_PU") (pin "2") (pinfunction "2_2") (pintype "passive"))
    )
    (net (code "12") (name "/JS1_RT_SIG") (class "Default")
      (node (ref "JS1_RT_IN") (pin "1") (pinfunction "1_1") (pintype "passive"))
      (node (ref "JS1_RT_PU") (pin "2") (pinfunction "2_2") (pintype "passive"))
    )
    (net (code "13") (name "/JS1_UP_SIG") (class "Default")
      (node (ref "JS1_UP_IN") (pin "1") (pinfunction "1_1") (pintype "passive"))
      (node (ref "JS1_UP_PU") (pin "2") (pinfunction "2_2") (pintype "passive"))
    )
    (net (code "14") (name "/JS2_DN_SIG") (class "Default")
      (node (ref "JS2_DN_BUT_2_SB") (pin "2") (pinfunction "1_2") (pintype "passive"))
      (node (ref "JS2_DN_IN") (pin "1") (pinfunction "1_1") (pintype "passive"))
      (node (ref "JS2_DN_PU") (pin "2") (pinfunction "2_2") (pintype "passive"))
    )
    (net (code "15") (name "/JS2_LT_SIG") (class "Default")
      (node (ref "JS2_LT_BUT_1_SB") (pin "2") (pinfunction "1_2") (pintype "passive"))
      (node (ref "JS2_LT_IN") (pin "1") (pinfunction "1_1") (pintype "passive"))
      (node (ref "JS2_LT_PU") (pin "2") (pinfunction "2_2") (pintype "passive"))
    )
    (net (code "16") (name "/JS2_RT_SIG") (class "Default")
      (node (ref "JS2_RT_BUT_4_SB") (pin "2") (pinfunction "1_2") (pintype "passive"))
      (node (ref "JS2_RT_IN") (pin "1") (pinfunction "1_1") (pintype "passive"))
      (node (ref "JS2_RT_PU") (pin "2") (pinfunction "2_2") (pintype "passive"))
    )
    (net (code "17") (name "/JS2_UP_SIG") (class "Default")
      (node (ref "JS2_UP_BUT_3_SB") (pin "2") (pinfunction "1_2") (pintype "passive"))
      (node (ref "JS2_UP_IN") (pin "1") (pinfunction "1_1") (pintype "passive"))
      (node (ref "JS2_UP_PU") (pin "2") (pinfunction "2_2") (pintype "passive"))
    )
    (net (code "18") (name "/LED_IN") (class "Default")
      (node (ref "CN_LED_IN") (pin "3") (pinfunction "3_3") (pintype "passive"))
      (node (ref "R1") (pin "2") (pinfunction "2_2") (pintype "passive"))
    )
    (net (code "19") (name "5V") (class "Default")
      (node (ref "C01") (pin "1") (pinfunction "1_1") (pintype "passive"))
      (node (ref "C02") (pin "1") (pinfunction "1_1") (pintype "passive"))
      (node (ref "C03") (pin "1") (pinfunction "1_1") (pintype "passive"))
      (node (ref "C04") (pin "1") (pinfunction "1_1") (pintype "passive"))
      (node (ref "C05") (pin "1") (pinfunction "1_1") (pintype "passive"))
      (node (ref "C06") (pin "1") (pinfunction "1_1") (pintype "passive"))
      (node (ref "C07") (pin "1") (pinfunction "1_1") (pintype "passive"))
      (node (ref "C08") (pin "1") (pinfunction "1_1") (pintype "passive"))
      (node (ref "C09") (pin "1") (pinfunction "1_1") (pintype "passive"))
      (node (ref "C10") (pin "1") (pinfunction "1_1") (pintype "passive"))
      (node (ref "C11") (pin "1") (pinfunction "1_1") (pintype "passive"))
      (node (ref "C12") (pin "1") (pinfunction "1_1") (pintype "passive"))
      (node (ref "C13") (pin "1") (pinfunction "1_1") (pintype "passive"))
      (node (ref "C14") (pin "1") (pinfunction "1_1") (pintype "passive"))
      (node (ref "C15") (pin "1") (pinfunction "1_1") (pintype "passive"))
      (node (ref "C16") (pin "1") (pinfunction "1_1") (pintype "passive"))
      (node (ref "C17") (pin "1") (pinfunction "1_1") (pintype "passive"))
      (node (ref "C18") (pin "1") (pinfunction "1_1") (pintype "passive"))
      (node (ref "C19") (pin "1") (pinfunction "1_1") (pintype "passive"))
      (node (ref "C20") (pin "1") (pinfunction "1_1") (pintype "passive"))
      (node (ref "C21") (pin "1") (pinfunction "1_1") (pintype "passive"))
      (node (ref "C22") (pin "1") (pinfunction "1_1") (pintype "passive"))
      (node (ref "C23") (pin "1") (pinfunction "1_1") (pintype "passive"))
      (node (ref "C24") (pin "1") (pinfunction "1_1") (pintype "passive"))
      (node (ref "C25") (pin "1") (pinfunction "1_1") (pintype "passive"))
      (node (ref "C26") (pin "1") (pinfunction "1_1") (pintype "passive"))
      (node (ref "C27") (pin "1") (pinfunction "1_1") (pintype "passive"))
      (node (ref "C28") (pin "1") (pinfunction "1_1") (pintype "passive"))
      (node (ref "C29") (pin "1") (pinfunction "1_1") (pintype "passive"))
      (node (ref "C30") (pin "1") (pinfunction "1_1") (pintype "passive"))
      (node (ref "C31") (pin "1") (pinfunction "1_1") (pintype "passive"))
      (node (ref "C32") (pin "1") (pinfunction "1_1") (pintype "passive"))
      (node (ref "CN_LED_IN") (pin "1") (pinfunction "1_1") (pintype "passive"))
      (node (ref "CN_LED_OUT") (pin "1") (pinfunction "1_1") (pintype "passive"))
      (node (ref "LED01") (pin "2") (pinfunction "VDD_2") (pintype "power_in"))
      (node (ref "LED02") (pin "2") (pinfunction "VDD_2") (pintype "power_in"))
      (node (ref "LED03") (pin "2") (pinfunction "VDD_2") (pintype "power_in"))
      (node (ref "LED04") (pin "2") (pinfunction "VDD_2") (pintype "power_in"))
      (node (ref "LED05") (pin "2") (pinfunction "VDD_2") (pintype "power_in"))
      (node (ref "LED06") (pin "2") (pinfunction "VDD_2") (pintype "power_in"))
      (node (ref "LED07") (pin "2") (pinfunction "VDD_2") (pintype "power_in"))
      (node (ref "LED08") (pin "2") (pinfunction "VDD_2") (pintype "power_in"))
      (node (ref "LED09") (pin "2") (pinfunction "VDD_2") (pintype "power_in"))
      (node (ref "LED10") (pin "2") (pinfunction "VDD_2") (pintype "power_in"))
      (node (ref "LED11") (pin "2") (pinfunction "VDD_2") (pintype "power_in"))
      (node (ref "LED12") (pin "2") (pinfunction "VDD_2") (pintype "power_in"))
      (node (ref "LED13") (pin "2") (pinfunction "VDD_2") (pintype "power_in"))
      (node (ref "LED14") (pin "2") (pinfunction "VDD_2") (pintype "power_in"))
      (node (ref "LED15") (pin "2") (pinfunction "VDD_2") (pintype "power_in"))
      (node (ref "LED16") (pin "2") (pinfunction "VDD_2") (pintype "power_in"))
      (node (ref "LED17") (pin "2") (pinfunction "VDD_2") (pintype "power_in"))
      (node (ref "LED18") (pin "2") (pinfunction "VDD_2") (pintype "power_in"))
      (node (ref "LED19") (pin "2") (pinfunction "VDD_2") (pintype "power_in"))
      (node (ref "LED20") (pin "2") (pinfunction "VDD_2") (pintype "power_in"))
      (node (ref "LED21") (pin "2") (pinfunction "VDD_2") (pintype "power_in"))
      (node (ref "LED22") (pin "2") (pinfunction "VDD_2") (pintype "power_in"))
      (node (ref "LED23") (pin "2") (pinfunction "VDD_2") (pintype "power_in"))
      (node (ref "LED24") (pin "2") (pinfunction "VDD_2") (pintype "power_in"))
      (node (ref "LED25") (pin "2") (pinfunction "VDD_2") (pintype "power_in"))
      (node (ref "LED26") (pin "2") (pinfunction "VDD_2") (pintype "power_in"))
      (node (ref "LED27") (pin "2") (pinfunction "VDD_2") (pintype "power_in"))
      (node (ref "LED28") (pin "2") (pinfunction "VDD_2") (pintype "power_in"))
      (node (ref "LED29") (pin "2") (pinfunction "VDD_2") (pintype "power_in"))
      (node (ref "LED30") (pin "2") (pinfunction "VDD_2") (pintype "power_in"))
      (node (ref "LED31") (pin "2") (pinfunction "VDD_2") (pintype "power_in"))
      (node (ref "LED32") (pin "2") (pinfunction "VDD_2") (pintype "power_in"))
    )
    (net (code "20") (name "GND") (class "Default")
      (node (ref "BUT_1_IN") (pin "2") (pinfunction "2_2") (pintype "passive"))
      (node (ref "BUT_2_IN") (pin "2") (pinfunction "2_2") (pintype "passive"))
      (node (ref "BUT_3_IN") (pin "2") (pinfunction "2_2") (pintype "passive"))
      (node (ref "BUT_4_IN") (pin "2") (pinfunction "2_2") (pintype "passive"))
      (node (ref "BUT_5_IN") (pin "2") (pinfunction "2_2") (pintype "passive"))
      (node (ref "BUT_6_IN") (pin "2") (pinfunction "2_2") (pintype "passive"))
      (node (ref "BUT_7_IN") (pin "2") (pinfunction "2_2") (pintype "passive"))
      (node (ref "BUT_8_IN") (pin "2") (pinfunction "2_2") (pintype "passive"))
      (node (ref "C01") (pin "2") (pinfunction "2_2") (pintype "passive"))
      (node (ref "C02") (pin "2") (pinfunction "2_2") (pintype "passive"))
      (node (ref "C03") (pin "2") (pinfunction "2_2") (pintype "passive"))
      (node (ref "C04") (pin "2") (pinfunction "2_2") (pintype "passive"))
      (node (ref "C05") (pin "2") (pinfunction "2_2") (pintype "passive"))
      (node (ref "C06") (pin "2") (pinfunction "2_2") (pintype "passive"))
      (node (ref "C07") (pin "2") (pinfunction "2_2") (pintype "passive"))
      (node (ref "C08") (pin "2") (pinfunction "2_2") (pintype "passive"))
      (node (ref "C09") (pin "2") (pinfunction "2_2") (pintype "passive"))
      (node (ref "C10") (pin "2") (pinfunction "2_2") (pintype "passive"))
      (node (ref "C11") (pin "2") (pinfunction "2_2") (pintype "passive"))
      (node (ref "C12") (pin "2") (pinfunction "2_2") (pintype "passive"))
      (node (ref "C13") (pin "2") (pinfunction "2_2") (pintype "passive"))
      (node (ref "C14") (pin "2") (pinfunction "2_2") (pintype "passive"))
      (node (ref "C15") (pin "2") (pinfunction "2_2") (pintype "passive"))
      (node (ref "C16") (pin "2") (pinfunction "2_2") (pintype "passive"))
      (node (ref "C17") (pin "2") (pinfunction "2_2") (pintype "passive"))
      (node (ref "C18") (pin "2") (pinfunction "2_2") (pintype "passive"))
      (node (ref "C19") (pin "2") (pinfunction "2_2") (pintype "passive"))
      (node (ref "C20") (pin "2") (pinfunction "2_2") (pintype "passive"))
      (node (ref "C21") (pin "2") (pinfunction "2_2") (pintype "passive"))
      (node (ref "C22") (pin "2") (pinfunction "2_2") (pintype "passive"))
      (node (ref "C23") (pin "2") (pinfunction "2_2") (pintype "passive"))
      (node (ref "C24") (pin "2") (pinfunction "2_2") (pintype "passive"))
      (node (ref "C25") (pin "2") (pinfunction "2_2") (pintype "passive"))
      (node (ref "C26") (pin "2") (pinfunction "2_2") (pintype "passive"))
      (node (ref "C27") (pin "2") (pinfunction "2_2") (pintype "passive"))
      (node (ref "C28") (pin "2") (pinfunction "2_2") (pintype "passive"))
      (node (ref "C29") (pin "2") (pinfunction "2_2") (pintype "passive"))
      (node (ref "C30") (pin "2") (pinfunction "2_2") (pintype "passive"))
      (node (ref "C31") (pin "2") (pinfunction "2_2") (pintype "passive"))
      (node (ref "C32") (pin "2") (pinfunction "2_2") (pintype "passive"))
      (node (ref "CN_LED_IN") (pin "0") (pinfunction "0_0") (pintype "passive"))
      (node (ref "CN_LED_IN") (pin "2") (pinfunction "2_2") (pintype "passive"))
      (node (ref "CN_LED_OUT") (pin "0") (pinfunction "0_0") (pintype "passive"))
      (node (ref "CN_LED_OUT") (pin "2") (pinfunction "2_2") (pintype "passive"))
      (node (ref "JS1_DN_IN") (pin "2") (pinfunction "2_2") (pintype "passive"))
      (node (ref "JS1_LT_IN") (pin "2") (pinfunction "2_2") (pintype "passive"))
      (node (ref "JS1_RT_IN") (pin "2") (pinfunction "2_2") (pintype "passive"))
      (node (ref "JS1_UP_IN") (pin "2") (pinfunction "2_2") (pintype "passive"))
      (node (ref "JS2_DN_IN") (pin "2") (pinfunction "2_2") (pintype "passive"))
      (node (ref "JS2_LT_IN") (pin "2") (pinfunction "2_2") (pintype "passive"))
      (node (ref "JS2_RT_IN") (pin "2") (pinfunction "2_2") (pintype "passive"))
      (node (ref "JS2_UP_IN") (pin "2") (pinfunction "2_2") (pintype "passive"))
      (node (ref "LED01") (pin "4") (pinfunction "GND_4") (pintype "passive"))
      (node (ref "LED02") (pin "4") (pinfunction "GND_4") (pintype "passive"))
      (node (ref "LED03") (pin "4") (pinfunction "GND_4") (pintype "passive"))
      (node (ref "LED04") (pin "4") (pinfunction "GND_4") (pintype "passive"))
      (node (ref "LED05") (pin "4") (pinfunction "GND_4") (pintype "passive"))
      (node (ref "LED06") (pin "4") (pinfunction "GND_4") (pintype "passive"))
      (node (ref "LED07") (pin "4") (pinfunction "GND_4") (pintype "passive"))
      (node (ref "LED08") (pin "4") (pinfunction "GND_4") (pintype "passive"))
      (node (ref "LED09") (pin "4") (pinfunction "GND_4") (pintype "passive"))
      (node (ref "LED10") (pin "4") (pinfunction "GND_4") (pintype "passive"))
      (node (ref "LED11") (pin "4") (pinfunction "GND_4") (pintype "passive"))
      (node (ref "LED12") (pin "4") (pinfunction "GND_4") (pintype "passive"))
      (node (ref "LED13") (pin "4") (pinfunction "GND_4") (pintype "passive"))
      (node (ref "LED14") (pin "4") (pinfunction "GND_4") (pintype "passive"))
      (node (ref "LED15") (pin "4") (pinfunction "GND_4") (pintype "passive"))
      (node (ref "LED16") (pin "4") (pinfunction "GND_4") (pintype "passive"))
      (node (ref "LED17") (pin "4") (pinfunction "GND_4") (pintype "passive"))
      (node (ref "LED18") (pin "4") (pinfunction "GND_4") (pintype "passive"))
      (node (ref "LED19") (pin "4") (pinfunction "GND_4") (pintype "passive"))
      (node (ref "LED20") (pin "4") (pinfunction "GND_4") (pintype "passive"))
      (node (ref "LED21") (pin "4") (pinfunction "GND_4") (pintype "passive"))
      (node (ref "LED22") (pin "4") (pinfunction "GND_4") (pintype "passive"))
      (node (ref "LED23") (pin "4") (pinfunction "GND_4") (pintype "passive"))
      (node (ref "LED24") (pin "4") (pinfunction "GND_4") (pintype "passive"))
      (node (ref "LED25") (pin "4") (pinfunction "GND_4") (pintype "passive"))
      (node (ref "LED26") (pin "4") (pinfunction "GND_4") (pintype "passive"))
      (node (ref "LED27") (pin "4") (pinfunction "GND_4") (pintype "passive"))
      (node (ref "LED28") (pin "4") (pinfunction "GND_4") (pintype "passive"))
      (node (ref "LED29") (pin "4") (pinfunction "GND_4") (pintype "passive"))
      (node (ref "LED30") (pin "4") (pinfunction "GND_4") (pintype "passive"))
      (node (ref "LED31") (pin "4") (pinfunction "GND_4") (pintype "passive"))
      (node (ref "LED32") (pin "4") (pinfunction "GND_4") (pintype "passive"))
    )
    (net (code "21") (name "Net-(LED01-DIN)") (class "Default")
      (node (ref "LED01") (pin "1") (pinfunction "DIN_1") (pintype "power_in"))
      (node (ref "R1") (pin "1") (pinfunction "1_1") (pintype "passive"))
    )
    (net (code "22") (name "Net-(LED01-DOUT)") (class "Default")
      (node (ref "LED01") (pin "3") (pinfunction "DOUT_3") (pintype "power_in"))
      (node (ref "LED02") (pin "1") (pinfunction "DIN_1") (pintype "power_in"))
      (node (ref "LED02_SKIP") (pin "1") (pinfunction "0_1") (pintype "passive"))
    )
    (net (code "23") (name "Net-(LED02-DOUT)") (class "Default")
      (node (ref "LED02") (pin "3") (pinfunction "DOUT_3") (pintype "power_in"))
      (node (ref "LED02_SKIP") (pin "2") (pinfunction "1_2") (pintype "passive"))
      (node (ref "LED03") (pin "1") (pinfunction "DIN_1") (pintype "power_in"))
    )
    (net (code "24") (name "Net-(LED03-DOUT)") (class "Default")
      (node (ref "LED03") (pin "3") (pinfunction "DOUT_3") (pintype "power_in"))
      (node (ref "LED04") (pin "1") (pinfunction "DIN_1") (pintype "power_in"))
      (node (ref "LED04_SKIP") (pin "1") (pinfunction "0_1") (pintype "passive"))
    )
    (net (code "25") (name "Net-(LED04-DOUT)") (class "Default")
      (node (ref "LED04") (pin "3") (pinfunction "DOUT_3") (pintype "power_in"))
      (node (ref "LED04_SKIP") (pin "2") (pinfunction "1_2") (pintype "passive"))
      (node (ref "LED05") (pin "1") (pinfunction "DIN_1") (pintype "power_in"))
    )
    (net (code "26") (name "Net-(LED05-DOUT)") (class "Default")
      (node (ref "LED05") (pin "3") (pinfunction "DOUT_3") (pintype "power_in"))
      (node (ref "LED06") (pin "1") (pinfunction "DIN_1") (pintype "power_in"))
      (node (ref "LED06_SKIP") (pin "1") (pinfunction "0_1") (pintype "passive"))
    )
    (net (code "27") (name "Net-(LED06-DOUT)") (class "Default")
      (node (ref "LED06") (pin "3") (pinfunction "DOUT_3") (pintype "power_in"))
      (node (ref "LED06_SKIP") (pin "2") (pinfunction "1_2") (pintype "passive"))
      (node (ref "LED07") (pin "1") (pinfunction "DIN_1") (pintype "power_in"))
    )
    (net (code "28") (name "Net-(LED07-DOUT)") (class "Default")
      (node (ref "LED07") (pin "3") (pinfunction "DOUT_3") (pintype "power_in"))
      (node (ref "LED08") (pin "1") (pinfunction "DIN_1") (pintype "power_in"))
      (node (ref "LED08_SKIP") (pin "1") (pinfunction "0_1") (pintype "passive"))
    )
    (net (code "29") (name "Net-(LED08-DOUT)") (class "Default")
      (node (ref "LED08") (pin "3") (pinfunction "DOUT_3") (pintype "power_in"))
      (node (ref "LED08_SKIP") (pin "2") (pinfunction "1_2") (pintype "passive"))
      (node (ref "LED09") (pin "1") (pinfunction "DIN_1") (pintype "power_in"))
    )
    (net (code "30") (name "Net-(LED09-DOUT)") (class "Default")
      (node (ref "LED09") (pin "3") (pinfunction "DOUT_3") (pintype "power_in"))
      (node (ref "LED10") (pin "1") (pinfunction "DIN_1") (pintype "power_in"))
      (node (ref "LED10_SKIP") (pin "2") (pinfunction "1_2") (pintype "passive"))
    )
    (net (code "31") (name "Net-(LED10-DOUT)") (class "Default")
      (node (ref "LED10") (pin "3") (pinfunction "DOUT_3") (pintype "power_in"))
      (node (ref "LED10_SKIP") (pin "1") (pinfunction "0_1") (pintype "passive"))
      (node (ref "LED11") (pin "1") (pinfunction "DIN_1") (pintype "power_in"))
    )
    (net (code "32") (name "Net-(LED11-DOUT)") (class "Default")
      (node (ref "LED11") (pin "3") (pinfunction "DOUT_3") (pintype "power_in"))
      (node (ref "LED12") (pin "1") (pinfunction "DIN_1") (pintype "power_in"))
      (node (ref "LED12_SKIP") (pin "2") (pinfunction "1_2") (pintype "passive"))
    )
    (net (code "33") (name "Net-(LED12-DOUT)") (class "Default")
      (node (ref "LED12") (pin "3") (pinfunction "DOUT_3") (pintype "power_in"))
      (node (ref "LED12_SKIP") (pin "1") (pinfunction "0_1") (pintype "passive"))
      (node (ref "LED13") (pin "1") (pinfunction "DIN_1") (pintype "power_in"))
    )
    (net (code "34") (name "Net-(LED13-DOUT)") (class "Default")
      (node (ref "LED13") (pin "3") (pinfunction "DOUT_3") (pintype "power_in"))
      (node (ref "LED14") (pin "1") (pinfunction "DIN_1") (pintype "power_in"))
      (node (ref "LED14_SKIP") (pin "2") (pinfunction "1_2") (pintype "passive"))
    )
    (net (code "35") (name "Net-(LED14-DOUT)") (class "Default")
      (node (ref "LED14") (pin "3") (pinfunction "DOUT_3") (pintype "power_in"))
      (node (ref "LED14_SKIP") (pin "1") (pinfunction "0_1") (pintype "passive"))
      (node (ref "LED15") (pin "1") (pinfunction "DIN_1") (pintype "power_in"))
    )
    (net (code "36") (name "Net-(LED15-DOUT)") (class "Default")
      (node (ref "LED15") (pin "3") (pinfunction "DOUT_3") (pintype "power_in"))
      (node (ref "LED16") (pin "1") (pinfunction "DIN_1") (pintype "power_in"))
      (node (ref "LED16_SKIP") (pin "2") (pinfunction "1_2") (pintype "passive"))
    )
    (net (code "37") (name "Net-(LED16-DOUT)") (class "Default")
      (node (ref "LED16") (pin "3") (pinfunction "DOUT_3") (pintype "power_in"))
      (node (ref "LED16_SKIP") (pin "1") (pinfunction "0_1") (pintype "passive"))
      (node (ref "LED17") (pin "1") (pinfunction "DIN_1") (pintype "power_in"))
    )
    (net (code "38") (name "Net-(LED17-DOUT)") (class "Default")
      (node (ref "LED17") (pin "3") (pinfunction "DOUT_3") (pintype "power_in"))
      (node (ref "LED18") (pin "1") (pinfunction "DIN_1") (pintype "power_in"))
      (node (ref "LED18_SKIP") (pin "1") (pinfunction "0_1") (pintype "passive"))
    )
    (net (code "39") (name "Net-(LED18-DOUT)") (class "Default")
      (node (ref "LED18") (pin "3") (pinfunction "DOUT_3") (pintype "power_in"))
      (node (ref "LED18_SKIP") (pin "2") (pinfunction "1_2") (pintype "passive"))
      (node (ref "LED19") (pin "1") (pinfunction "DIN_1") (pintype "power_in"))
    )
    (net (code "40") (name "Net-(LED19-DOUT)") (class "Default")
      (node (ref "LED19") (pin "3") (pinfunction "DOUT_3") (pintype "power_in"))
      (node (ref "LED20") (pin "1") (pinfunction "DIN_1") (pintype "power_in"))
      (node (ref "LED20_SKIP") (pin "1") (pinfunction "0_1") (pintype "passive"))
    )
    (net (code "41") (name "Net-(LED20-DOUT)") (class "Default")
      (node (ref "LED20") (pin "3") (pinfunction "DOUT_3") (pintype "power_in"))
      (node (ref "LED20_SKIP") (pin "2") (pinfunction "1_2") (pintype "passive"))
      (node (ref "LED21") (pin "1") (pinfunction "DIN_1") (pintype "power_in"))
    )
    (net (code "42") (name "Net-(LED21-DOUT)") (class "Default")
      (node (ref "LED21") (pin "3") (pinfunction "DOUT_3") (pintype "power_in"))
      (node (ref "LED22") (pin "1") (pinfunction "DIN_1") (pintype "power_in"))
      (node (ref "LED22_SKIP") (pin "1") (pinfunction "0_1") (pintype "passive"))
    )
    (net (code "43") (name "Net-(LED22-DOUT)") (class "Default")
      (node (ref "LED22") (pin "3") (pinfunction "DOUT_3") (pintype "power_in"))
      (node (ref "LED22_SKIP") (pin "2") (pinfunction "1_2") (pintype "passive"))
      (node (ref "LED23") (pin "1") (pinfunction "DIN_1") (pintype "power_in"))
    )
    (net (code "44") (name "Net-(LED23-DOUT)") (class "Default")
      (node (ref "LED23") (pin "3") (pinfunction "DOUT_3") (pintype "power_in"))
      (node (ref "LED24") (pin "1") (pinfunction "DIN_1") (pintype "power_in"))
      (node (ref "LED24_SKIP") (pin "1") (pinfunction "0_1") (pintype "passive"))
    )
    (net (code "45") (name "Net-(LED24-DOUT)") (class "Default")
      (node (ref "LED24") (pin "3") (pinfunction "DOUT_3") (pintype "power_in"))
      (node (ref "LED24_SKIP") (pin "2") (pinfunction "1_2") (pintype "passive"))
      (node (ref "LED25") (pin "1") (pinfunction "DIN_1") (pintype "power_in"))
    )
    (net (code "46") (name "Net-(LED25-DOUT)") (class "Default")
      (node (ref "LED25") (pin "3") (pinfunction "DOUT_3") (pintype "power_in"))
      (node (ref "LED26") (pin "1") (pinfunction "DIN_1") (pintype "power_in"))
      (node (ref "LED26_SKIP") (pin "2") (pinfunction "1_2") (pintype "passive"))
    )
    (net (code "47") (name "Net-(LED26-DOUT)") (class "Default")
      (node (ref "LED26") (pin "3") (pinfunction "DOUT_3") (pintype "power_in"))
      (node (ref "LED26_SKIP") (pin "1") (pinfunction "0_1") (pintype "passive"))
      (node (ref "LED27") (pin "1") (pinfunction "DIN_1") (pintype "power_in"))
    )
    (net (code "48") (name "Net-(LED27-DOUT)") (class "Default")
      (node (ref "LED27") (pin "3") (pinfunction "DOUT_3") (pintype "power_in"))
      (node (ref "LED28") (pin "1") (pinfunction "DIN_1") (pintype "power_in"))
      (node (ref "LED28_SKIP") (pin "2") (pinfunction "1_2") (pintype "passive"))
    )
    (net (code "49") (name "Net-(LED28-DOUT)") (class "Default")
      (node (ref "LED28") (pin "3") (pinfunction "DOUT_3") (pintype "power_in"))
      (node (ref "LED28_SKIP") (pin "1") (pinfunction "0_1") (pintype "passive"))
      (node (ref "LED29") (pin "1") (pinfunction "DIN_1") (pintype "power_in"))
    )
    (net (code "50") (name "Net-(LED29-DOUT)") (class "Default")
      (node (ref "LED29") (pin "3") (pinfunction "DOUT_3") (pintype "power_in"))
      (node (ref "LED30") (pin "1") (pinfunction "DIN_1") (pintype "power_in"))
      (node (ref "LED30_SKIP") (pin "2") (pinfunction "1_2") (pintype "passive"))
    )
    (net (code "51") (name "Net-(LED30-DOUT)") (class "Default")
      (node (ref "LED30") (pin "3") (pinfunction "DOUT_3") (pintype "power_in"))
      (node (ref "LED30_SKIP") (pin "1") (pinfunction "0_1") (pintype "passive"))
      (node (ref "LED31") (pin "1") (pinfunction "DIN_1") (pintype "power_in"))
    )
    (net (code "52") (name "Net-(LED31-DOUT)") (class "Default")
      (node (ref "LED31") (pin "3") (pinfunction "DOUT_3") (pintype "power_in"))
      (node (ref "LED32") (pin "1") (pinfunction "DIN_1") (pintype "power_in"))
      (node (ref "LED32_SKIP") (pin "2") (pinfunction "1_2") (pintype "passive"))
    )
    (net (code "53") (name "VCCIO") (class "Default")
      (node (ref "BUT_1_PU") (pin "1") (pinfunction "1_1") (pintype "passive"))
      (node (ref "BUT_2_PU") (pin "1") (pinfunction "1_1") (pintype "passive"))
      (node (ref "BUT_3_PU") (pin "1") (pinfunction "1_1") (pintype "passive"))
      (node (ref "BUT_4_PU") (pin "1") (pinfunction "1_1") (pintype "passive"))
      (node (ref "BUT_5_PU") (pin "1") (pinfunction "1_1") (pintype "passive"))
      (node (ref "BUT_6_PU") (pin "1") (pinfunction "1_1") (pintype "passive"))
      (node (ref "BUT_7_UP") (pin "1") (pinfunction "1_1") (pintype "passive"))
      (node (ref "BUT_8_PU") (pin "1") (pinfunction "1_1") (pintype "passive"))
      (node (ref "JS1_DN_PU") (pin "1") (pinfunction "1_1") (pintype "passive"))
      (node (ref "JS1_LT_PU") (pin "1") (pinfunction "1_1") (pintype "passive"))
      (node (ref "JS1_RT_PU") (pin "1") (pinfunction "1_1") (pintype "passive"))
      (node (ref "JS1_UP_PU") (pin "1") (pinfunction "1_1") (pintype "passive"))
      (node (ref "JS2_DN_PU") (pin "1") (pinfunction "1_1") (pintype "passive"))
      (node (ref "JS2_LT_PU") (pin "1") (pinfunction "1_1") (pintype "passive"))
      (node (ref "JS2_RT_PU") (pin "1") (pinfunction "1_1") (pintype "passive"))
      (node (ref "JS2_UP_PU") (pin "1") (pinfunction "1_1") (pintype "passive"))
    )
  )
)
